# TwoButton.net
KiCad netlist of a schematic drawn in Altium Designer
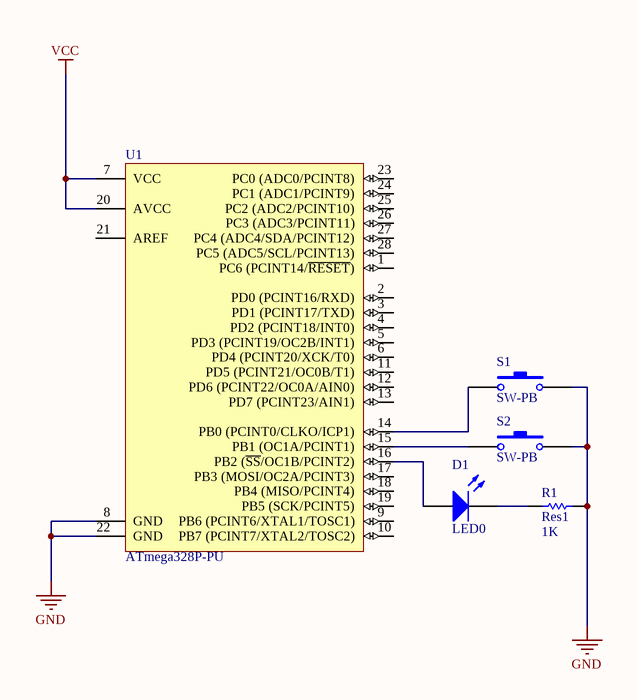
[diagram p0: TwoButton.SchDoc]

(export (version "E")
  (design (tool "Eeschema 10.0.6"))
  (components
    (comp (ref "D1")
      (value "LED0")
      (footprint "LED-0")
      (description "Typical INFRARED GaAs LED")
      (fields (field (name "PUBLISHER") "Altium Limited"))
      (libsource (lib "Miscellaneous Devices") (part "LED0"))
    )
    (comp (ref "R1")
      (value "Res1")
      (footprint "AXIAL-0.3")
      (description "Resistor")
      (fields (field (name "ALTIUM_VALUE") "1K") (field (name "PUBLISHER") "Altium Limited"))
      (libsource (lib "Miscellaneous Devices") (part "Res1"))
    )
    (comp (ref "S1")
      (value "SW-PB")
      (footprint "SPST-2")
      (description "Switch")
      (fields (field (name "PUBLISHER") "Altium Limited"))
      (libsource (lib "Miscellaneous Devices") (part "SW-PB"))
    )
    (comp (ref "S2")
      (value "SW-PB")
      (footprint "SPST-2")
      (description "Switch")
      (fields (field (name "PUBLISHER") "Altium Limited"))
      (libsource (lib "Miscellaneous Devices") (part "SW-PB"))
    )
    (comp (ref "U1")
      (value "ATmega328P-PU")
      (footprint "28P3")
      (fields (field (name "PUBLISHER") "Altium Limited"))
      (libsource (lib "Atmel Microcontroller 8-Bit megaAVR") (part "ATmega328P-PU"))
    )
  )
  (nets
    (net (code "1") (name "GND") (class "Default")
      (node (ref "R1") (pin "2") (pinfunction "2_2") (pintype "passive"))
      (node (ref "S1") (pin "2") (pinfunction "2_2") (pintype "passive"))
      (node (ref "S2") (pin "2") (pinfunction "2_2") (pintype "passive"))
      (node (ref "U1") (pin "22") (pinfunction "GND_22") (pintype "power_in"))
      (node (ref "U1") (pin "8") (pinfunction "GND_8") (pintype "power_in"))
    )
    (net (code "2") (name "Net-(D1-A)") (class "Default")
      (node (ref "D1") (pin "1") (pinfunction "A_1") (pintype "passive"))
      (node (ref "U1") (pin "16") (pinfunction "PB2_(~{SS}/OC1B/PCINT2)_16") (pintype "bidirectional"))
    )
    (net (code "3") (name "Net-(D1-K)") (class "Default")
      (node (ref "D1") (pin "2") (pinfunction "K_2") (pintype "passive"))
      (node (ref "R1") (pin "1") (pinfunction "1_1") (pintype "passive"))
    )
    (net (code "4") (name "Net-(U1-PB0_(PCINT0{slash}CLKO{slash}ICP1))") (class "Default")
      (node (ref "S1") (pin "1") (pinfunction "1_1") (pintype "passive"))
      (node (ref "U1") (pin "14") (pinfunction "PB0_(PCINT0/CLKO/ICP1)_14") (pintype "bidirectional"))
    )
    (net (code "5") (name "Net-(U1-PB1_(OC1A{slash}PCINT1))") (class "Default")
      (node (ref "S2") (pin "1") (pinfunction "1_1") (pintype "passive"))
      (node (ref "U1") (pin "15") (pinfunction "PB1_(OC1A/PCINT1)_15") (pintype "bidirectional"))
    )
    (net (code "6") (name "VCC") (class "Default")
      (node (ref "U1") (pin "20") (pinfunction "AVCC_20") (pintype "power_in"))
      (node (ref "U1") (pin "7") (pinfunction "VCC_7") (pintype "power_in"))
    )
    (net (code "7") (name "unconnected-(U1-AREF-Pad21)") (class "Default")
      (node (ref "U1") (pin "21") (pinfunction "AREF_21") (pintype "power_in"))
    )
    (net (code "8") (name "unconnected-(U1-PB3_(MOSI{slash}OC2A{slash}PCINT3)-Pad17)") (class "Default")
      (node (ref "U1") (pin "17") (pinfunction "PB3_(MOSI/OC2A/PCINT3)_17") (pintype "bidirectional"))
    )
    (net (code "9") (name "unconnected-(U1-PB4_(MISO{slash}PCINT4)-Pad18)") (class "Default")
      (node (ref "U1") (pin "18") (pinfunction "PB4_(MISO/PCINT4)_18") (pintype "bidirectional"))
    )
    (net (code "10") (name "unconnected-(U1-PB5_(SCK{slash}PCINT5)-Pad19)") (class "Default")
      (node (ref "U1") (pin "19") (pinfunction "PB5_(SCK/PCINT5)_19") (pintype "bidirectional"))
    )
    (net (code "11") (name "unconnected-(U1-PB6_(PCINT6{slash}XTAL1{slash}TOSC1)-Pad9)") (class "Default")
      (node (ref "U1") (pin "9") (pinfunction "PB6_(PCINT6/XTAL1/TOSC1)_9") (pintype "bidirectional"))
    )
    (net (code "12") (name "unconnected-(U1-PB7_(PCINT7{slash}XTAL2{slash}TOSC2)-Pad10)") (class "Default")
      (node (ref "U1") (pin "10") (pinfunction "PB7_(PCINT7/XTAL2/TOSC2)_10") (pintype "bidirectional"))
    )
    (net (code "13") (name "unconnected-(U1-PC0_(ADC0{slash}PCINT8)-Pad23)") (class "Default")
      (node (ref "U1") (pin "23") (pinfunction "PC0_(ADC0/PCINT8)_23") (pintype "bidirectional"))
    )
    (net (code "14") (name "unconnected-(U1-PC1_(ADC1{slash}PCINT9)-Pad24)") (class "Default")
      (node (ref "U1") (pin "24") (pinfunction "PC1_(ADC1/PCINT9)_24") (pintype "bidirectional"))
    )
    (net (code "15") (name "unconnected-(U1-PC2_(ADC2{slash}PCINT10)-Pad25)") (class "Default")
      (node (ref "U1") (pin "25") (pinfunction "PC2_(ADC2/PCINT10)_25") (pintype "bidirectional"))
    )
    (net (code "16") (name "unconnected-(U1-PC3_(ADC3{slash}PCINT11)-Pad26)") (class "Default")
      (node (ref "U1") (pin "26") (pinfunction "PC3_(ADC3/PCINT11)_26") (pintype "bidirectional"))
    )
    (net (code "17") (name "unconnected-(U1-PC4_(ADC4{slash}SDA{slash}PCINT12)-Pad27)") (class "Default")
      (node (ref "U1") (pin "27") (pinfunction "PC4_(ADC4/SDA/PCINT12)_27") (pintype "bidirectional"))
    )
    (net (code "18") (name "unconnected-(U1-PC5_(ADC5{slash}SCL{slash}PCINT13)-Pad28)") (class "Default")
      (node (ref "U1") (pin "28") (pinfunction "PC5_(ADC5/SCL/PCINT13)_28") (pintype "bidirectional"))
    )
    (net (code "19") (name "unconnected-(U1-PC6_(PCINT14{slash}~{RESET})-Pad1)") (class "Default")
      (node (ref "U1") (pin "1") (pinfunction "PC6_(PCINT14/~{RESET})_1") (pintype "bidirectional"))
    )
    (net (code "20") (name "unconnected-(U1-PD0_(PCINT16{slash}RXD)-Pad2)") (class "Default")
      (node (ref "U1") (pin "2") (pinfunction "PD0_(PCINT16/RXD)_2") (pintype "bidirectional"))
    )
    (net (code "21") (name "unconnected-(U1-PD1_(PCINT17{slash}TXD)-Pad3)") (class "Default")
      (node (ref "U1") (pin "3") (pinfunction "PD1_(PCINT17/TXD)_3") (pintype "bidirectional"))
    )
    (net (code "22") (name "unconnected-(U1-PD2_(PCINT18{slash}INT0)-Pad4)") (class "Default")
      (node (ref "U1") (pin "4") (pinfunction "PD2_(PCINT18/INT0)_4") (pintype "bidirectional"))
    )
    (net (code "23") (name "unconnected-(U1-PD3_(PCINT19{slash}OC2B{slash}INT1)-Pad5)") (class "Default")
      (node (ref "U1") (pin "5") (pinfunction "PD3_(PCINT19/OC2B/INT1)_5") (pintype "bidirectional"))
    )
    (net (code "24") (name "unconnected-(U1-PD4_(PCINT20{slash}XCK{slash}T0)-Pad6)") (class "Default")
      (node (ref "U1") (pin "6") (pinfunction "PD4_(PCINT20/XCK/T0)_6") (pintype "bidirectional"))
    )
    (net (code "25") (name "unconnected-(U1-PD5_(PCINT21{slash}OC0B{slash}T1)-Pad11)") (class "Default")
      (node (ref "U1") (pin "11") (pinfunction "PD5_(PCINT21/OC0B/T1)_11") (pintype "bidirectional"))
    )
    (net (code "26") (name "unconnected-(U1-PD6_(PCINT22{slash}OC0A{slash}AIN0)-Pad12)") (class "Default")
      (node (ref "U1") (pin "12") (pinfunction "PD6_(PCINT22/OC0A/AIN0)_12") (pintype "bidirectional"))
    )
    (net (code "27") (name "unconnected-(U1-PD7_(PCINT23{slash}AIN1)-Pad13)") (class "Default")
      (node (ref "U1") (pin "13") (pinfunction "PD7_(PCINT23/AIN1)_13") (pintype "bidirectional"))
    )
  )
)
